# knitRider_exp_1_1.net
KiCad netlist of a schematic drawn in EAGLE
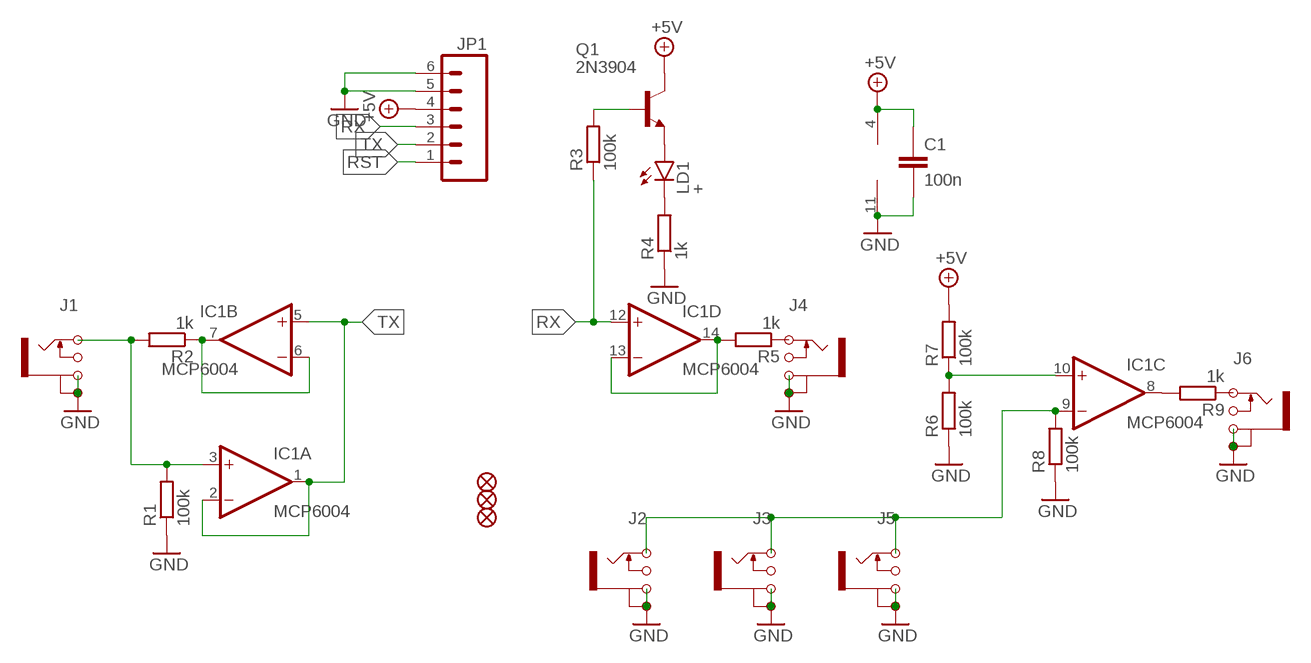
[diagram p0: schematic, sheet 1]

(export (version "E")
  (design (tool "Eeschema 10.0.6"))
  (components
    (comp (ref "C1")
      (value "100n")
      (footprint "eagle-import:CAPACITOR0603")
      (libsource (lib "eagle-import") (part "CAPACITOR0603"))
    )
    (comp (ref "FID1")
      (value "FIDUCIAL")
      (footprint "eagle-import:FIDUCIAL")
      (libsource (lib "eagle-import") (part "FIDUCIAL"))
    )
    (comp (ref "FID2")
      (value "FIDUCIAL")
      (footprint "eagle-import:FIDUCIAL")
      (libsource (lib "eagle-import") (part "FIDUCIAL"))
    )
    (comp (ref "FID3")
      (value "FIDUCIAL")
      (footprint "eagle-import:FIDUCIAL")
      (libsource (lib "eagle-import") (part "FIDUCIAL"))
    )
    (comp (ref "IC1")
      (value "MCP6004")
      (footprint "eagle-import:SO14")
      (fields (field (name "MPN") "MCP6004T-I/SL"))
      (libsource (lib "eagle-import") (part "MCP6004D"))
    )
    (comp (ref "J1")
      (value "JACK_MONOJACK_MONO")
      (footprint "eagle-import:JACK_MONO")
      (libsource (lib "eagle-import") (part "JACK_MONOJACK_MONO"))
    )
    (comp (ref "J2")
      (value "JACK_MONOJACK_MONO")
      (footprint "eagle-import:JACK_MONO")
      (libsource (lib "eagle-import") (part "JACK_MONOJACK_MONO"))
    )
    (comp (ref "J3")
      (value "JACK_MONOJACK_MONO")
      (footprint "eagle-import:JACK_MONO")
      (libsource (lib "eagle-import") (part "JACK_MONOJACK_MONO"))
    )
    (comp (ref "J4")
      (value "JACK_MONOJACK_MONO")
      (footprint "eagle-import:JACK_MONO")
      (libsource (lib "eagle-import") (part "JACK_MONOJACK_MONO"))
    )
    (comp (ref "J5")
      (value "JACK_MONOJACK_MONO")
      (footprint "eagle-import:JACK_MONO")
      (libsource (lib "eagle-import") (part "JACK_MONOJACK_MONO"))
    )
    (comp (ref "J6")
      (value "JACK_MONOJACK_MONO")
      (footprint "eagle-import:JACK_MONO")
      (libsource (lib "eagle-import") (part "JACK_MONOJACK_MONO"))
    )
    (comp (ref "JP1")
      (value "M06LOCK")
      (footprint "eagle-import:1X06_LOCK")
      (libsource (lib "eagle-import") (part "M06LOCK"))
    )
    (comp (ref "LD1")
      (value "+")
      (footprint "eagle-import:LEDSMALLHOLES")
      (libsource (lib "eagle-import") (part "LED_THT"))
    )
    (comp (ref "Q1")
      (value "2N3904")
      (footprint "eagle-import:SOT23")
      (fields (field (name "MPN") "MMBT3904LT1G"))
      (libsource (lib "eagle-import") (part "2N3904"))
    )
    (comp (ref "R1")
      (value "100k")
      (footprint "eagle-import:RESISTOR0603")
      (libsource (lib "eagle-import") (part "RESISTOR0603"))
    )
    (comp (ref "R2")
      (value "1k")
      (footprint "eagle-import:RESISTOR0603")
      (libsource (lib "eagle-import") (part "RESISTOR0603"))
    )
    (comp (ref "R3")
      (value "100k")
      (footprint "eagle-import:RESISTOR0603")
      (libsource (lib "eagle-import") (part "RESISTOR0603"))
    )
    (comp (ref "R4")
      (value "1k")
      (footprint "eagle-import:RESISTOR0603")
      (libsource (lib "eagle-import") (part "RESISTOR0603"))
    )
    (comp (ref "R5")
      (value "1k")
      (footprint "eagle-import:RESISTOR0603")
      (libsource (lib "eagle-import") (part "RESISTOR0603"))
    )
    (comp (ref "R6")
      (value "100k")
      (footprint "eagle-import:RESISTOR0603")
      (libsource (lib "eagle-import") (part "RESISTOR0603"))
    )
    (comp (ref "R7")
      (value "100k")
      (footprint "eagle-import:RESISTOR0603")
      (libsource (lib "eagle-import") (part "RESISTOR0603"))
    )
    (comp (ref "R8")
      (value "100k")
      (footprint "eagle-import:RESISTOR0603")
      (libsource (lib "eagle-import") (part "RESISTOR0603"))
    )
    (comp (ref "R9")
      (value "1k")
      (footprint "eagle-import:RESISTOR0603")
      (libsource (lib "eagle-import") (part "RESISTOR0603"))
    )
  )
  (nets
    (net (code "1") (name "+5V") (class "Default")
      (node (ref "C1") (pin "1") (pinfunction "1_1") (pintype "passive"))
      (node (ref "IC1") (pin "4") (pinfunction "V+_4") (pintype "power_in"))
      (node (ref "JP1") (pin "4") (pinfunction "4_4") (pintype "passive"))
      (node (ref "Q1") (pin "C") (pinfunction "C_C") (pintype "passive"))
      (node (ref "R7") (pin "2") (pinfunction "2_2") (pintype "passive"))
    )
    (net (code "2") (name "GND") (class "Default")
      (node (ref "C1") (pin "2") (pinfunction "2_2") (pintype "passive"))
      (node (ref "IC1") (pin "11") (pinfunction "V-_11") (pintype "power_in"))
      (node (ref "J1") (pin "G1") (pinfunction "G1_G1") (pintype "passive"))
      (node (ref "J1") (pin "G2") (pinfunction "G2_G2") (pintype "passive"))
      (node (ref "J2") (pin "G1") (pinfunction "G1_G1") (pintype "passive"))
      (node (ref "J2") (pin "G2") (pinfunction "G2_G2") (pintype "passive"))
      (node (ref "J3") (pin "G1") (pinfunction "G1_G1") (pintype "passive"))
      (node (ref "J3") (pin "G2") (pinfunction "G2_G2") (pintype "passive"))
      (node (ref "J4") (pin "G1") (pinfunction "G1_G1") (pintype "passive"))
      (node (ref "J4") (pin "G2") (pinfunction "G2_G2") (pintype "passive"))
      (node (ref "J5") (pin "G1") (pinfunction "G1_G1") (pintype "passive"))
      (node (ref "J5") (pin "G2") (pinfunction "G2_G2") (pintype "passive"))
      (node (ref "J6") (pin "G1") (pinfunction "G1_G1") (pintype "passive"))
      (node (ref "J6") (pin "G2") (pinfunction "G2_G2") (pintype "passive"))
      (node (ref "JP1") (pin "5") (pinfunction "5_5") (pintype "passive"))
      (node (ref "JP1") (pin "6") (pinfunction "6_6") (pintype "passive"))
      (node (ref "R1") (pin "1") (pinfunction "1_1") (pintype "passive"))
      (node (ref "R4") (pin "1") (pinfunction "1_1") (pintype "passive"))
      (node (ref "R6") (pin "1") (pinfunction "1_1") (pintype "passive"))
      (node (ref "R8") (pin "1") (pinfunction "1_1") (pintype "passive"))
    )
    (net (code "3") (name "Net-(IC1A-+IN)") (class "Default")
      (node (ref "IC1") (pin "3") (pinfunction "+IN_3") (pintype "input"))
      (node (ref "J1") (pin "T") (pinfunction "T_T") (pintype "passive"))
      (node (ref "R1") (pin "2") (pinfunction "2_2") (pintype "passive"))
      (node (ref "R2") (pin "2") (pinfunction "2_2") (pintype "passive"))
    )
    (net (code "4") (name "Net-(IC1B--IN)") (class "Default")
      (node (ref "IC1") (pin "6") (pinfunction "-IN_6") (pintype "input"))
      (node (ref "IC1") (pin "7") (pinfunction "OUT_7") (pintype "output"))
      (node (ref "R2") (pin "1") (pinfunction "1_1") (pintype "passive"))
    )
    (net (code "5") (name "Net-(IC1C-+IN)") (class "Default")
      (node (ref "IC1") (pin "10") (pinfunction "+IN_10") (pintype "input"))
      (node (ref "R6") (pin "2") (pinfunction "2_2") (pintype "passive"))
      (node (ref "R7") (pin "1") (pinfunction "1_1") (pintype "passive"))
    )
    (net (code "6") (name "Net-(IC1C--IN)") (class "Default")
      (node (ref "IC1") (pin "9") (pinfunction "-IN_9") (pintype "input"))
      (node (ref "J2") (pin "T") (pinfunction "T_T") (pintype "passive"))
      (node (ref "J3") (pin "T") (pinfunction "T_T") (pintype "passive"))
      (node (ref "J5") (pin "T") (pinfunction "T_T") (pintype "passive"))
      (node (ref "R8") (pin "2") (pinfunction "2_2") (pintype "passive"))
    )
    (net (code "7") (name "Net-(IC1C-OUT)") (class "Default")
      (node (ref "IC1") (pin "8") (pinfunction "OUT_8") (pintype "output"))
      (node (ref "R9") (pin "2") (pinfunction "2_2") (pintype "passive"))
    )
    (net (code "8") (name "Net-(IC1D--IN)") (class "Default")
      (node (ref "IC1") (pin "13") (pinfunction "-IN_13") (pintype "input"))
      (node (ref "IC1") (pin "14") (pinfunction "OUT_14") (pintype "output"))
      (node (ref "R5") (pin "2") (pinfunction "2_2") (pintype "passive"))
    )
    (net (code "9") (name "Net-(J4-PadT)") (class "Default")
      (node (ref "J4") (pin "T") (pinfunction "T_T") (pintype "passive"))
      (node (ref "R5") (pin "1") (pinfunction "1_1") (pintype "passive"))
    )
    (net (code "10") (name "Net-(J6-PadT)") (class "Default")
      (node (ref "J6") (pin "T") (pinfunction "T_T") (pintype "passive"))
      (node (ref "R9") (pin "1") (pinfunction "1_1") (pintype "passive"))
    )
    (net (code "11") (name "Net-(LD1-C)") (class "Default")
      (node (ref "LD1") (pin "K") (pinfunction "C_K") (pintype "passive"))
      (node (ref "R4") (pin "2") (pinfunction "2_2") (pintype "passive"))
    )
    (net (code "12") (name "Net-(LD1-PadA)") (class "Default")
      (node (ref "LD1") (pin "A") (pinfunction "A_A") (pintype "passive"))
      (node (ref "Q1") (pin "E") (pinfunction "E_E") (pintype "passive"))
    )
    (net (code "13") (name "Net-(Q1-PadB)") (class "Default")
      (node (ref "Q1") (pin "B") (pinfunction "B_B") (pintype "passive"))
      (node (ref "R3") (pin "2") (pinfunction "2_2") (pintype "passive"))
    )
    (net (code "14") (name "RST") (class "Default")
      (node (ref "JP1") (pin "1") (pinfunction "1_1") (pintype "passive"))
    )
    (net (code "15") (name "RX") (class "Default")
      (node (ref "IC1") (pin "12") (pinfunction "+IN_12") (pintype "input"))
      (node (ref "JP1") (pin "3") (pinfunction "3_3") (pintype "passive"))
      (node (ref "R3") (pin "1") (pinfunction "1_1") (pintype "passive"))
    )
    (net (code "16") (name "TX") (class "Default")
      (node (ref "IC1") (pin "1") (pinfunction "OUT_1") (pintype "output"))
      (node (ref "IC1") (pin "2") (pinfunction "-IN_2") (pintype "input"))
      (node (ref "IC1") (pin "5") (pinfunction "+IN_5") (pintype "input"))
      (node (ref "JP1") (pin "2") (pinfunction "2_2") (pintype "passive"))
    )
    (net (code "17") (name "unconnected-(J1-PadSW)") (class "Default")
      (node (ref "J1") (pin "SW") (pinfunction "SW_SW") (pintype "passive"))
    )
    (net (code "18") (name "unconnected-(J2-PadSW)") (class "Default")
      (node (ref "J2") (pin "SW") (pinfunction "SW_SW") (pintype "passive"))
    )
    (net (code "19") (name "unconnected-(J3-PadSW)") (class "Default")
      (node (ref "J3") (pin "SW") (pinfunction "SW_SW") (pintype "passive"))
    )
    (net (code "20") (name "unconnected-(J4-PadSW)") (class "Default")
      (node (ref "J4") (pin "SW") (pinfunction "SW_SW") (pintype "passive"))
    )
    (net (code "21") (name "unconnected-(J5-PadSW)") (class "Default")
      (node (ref "J5") (pin "SW") (pinfunction "SW_SW") (pintype "passive"))
    )
    (net (code "22") (name "unconnected-(J6-PadSW)") (class "Default")
      (node (ref "J6") (pin "SW") (pinfunction "SW_SW") (pintype "passive"))
    )
  )
)
